# BoardB-USB.net
KiCad netlist of a schematic drawn in Altium Designer
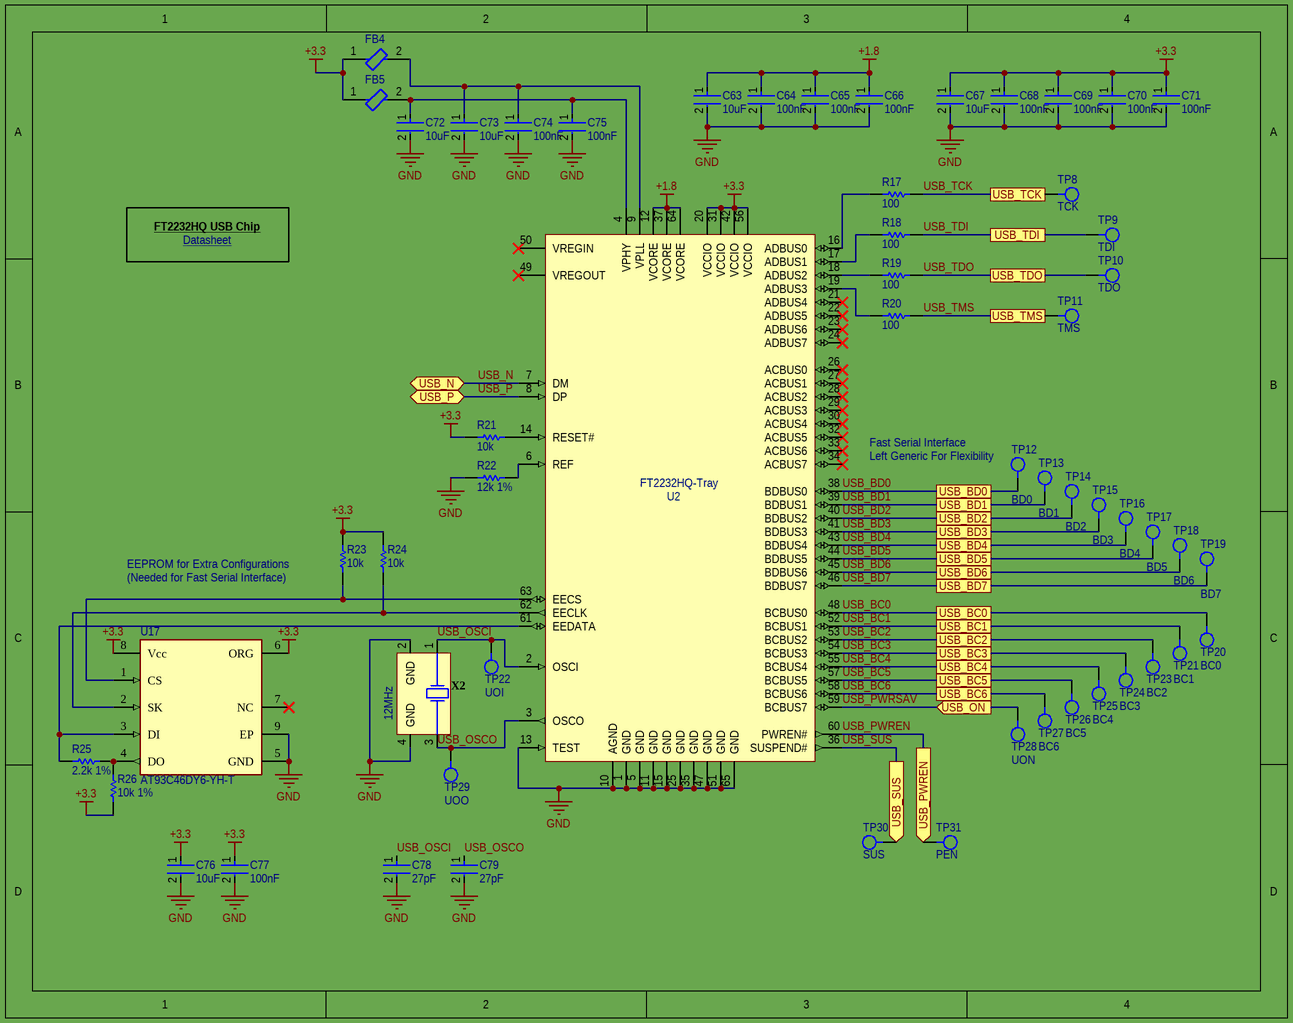
[diagram p0: BoardB-USB.SchDoc]

(export (version "E")
  (design (tool "Eeschema 10.0.6"))
  (components
    (comp (ref "C63")
      (value "10uF")
      (footprint "FP-GRM188-0_1-e0_2_0_55-IPC_A")
      (description "Chip Multilayer Ceramic Capacitors for General Purpose, 0603, 10uF, X5R, 15%, 20%, 6.3V")
      (fields (field (name "VOLTAGE") "6.3V") (field (name "TOLERANCE") "20%"))
      (libsource (lib "Altium Content Vault") (part "02cd4be3c70576c341d710602a673aa"))
    )
    (comp (ref "C64")
      (value "100nF")
      (footprint "FP-CGA3E-0_3-0_1-IPC_A")
      (description "Cap Ceramic 100nF 50V X7R 10% Pad SMD 0603 +125°C Automotive T/R")
      (fields (field (name "TOLERANCE") "10%") (field (name "VOLTAGE") "50V"))
      (libsource (lib "Altium Content Vault") (part "b4654b650e69147ec39a6b967a45e02"))
    )
    (comp (ref "C65")
      (value "100nF")
      (footprint "FP-CGA3E-0_3-0_1-IPC_A")
      (description "Cap Ceramic 100nF 50V X7R 10% Pad SMD 0603 +125°C Automotive T/R")
      (fields (field (name "TOLERANCE") "10%") (field (name "VOLTAGE") "50V"))
      (libsource (lib "Altium Content Vault") (part "b4654b650e69147ec39a6b967a45e02"))
    )
    (comp (ref "C66")
      (value "100nF")
      (footprint "FP-CGA3E-0_3-0_1-IPC_A")
      (description "Cap Ceramic 100nF 50V X7R 10% Pad SMD 0603 +125°C Automotive T/R")
      (fields (field (name "TOLERANCE") "10%") (field (name "VOLTAGE") "50V"))
      (libsource (lib "Altium Content Vault") (part "b4654b650e69147ec39a6b967a45e02"))
    )
    (comp (ref "C67")
      (value "10uF")
      (footprint "FP-GRM188-0_1-e0_2_0_55-IPC_A")
      (description "Chip Multilayer Ceramic Capacitors for General Purpose, 0603, 10uF, X5R, 15%, 20%, 6.3V")
      (fields (field (name "VOLTAGE") "6.3V") (field (name "TOLERANCE") "20%"))
      (libsource (lib "Altium Content Vault") (part "02cd4be3c70576c341d710602a673aa"))
    )
    (comp (ref "C68")
      (value "100nF")
      (footprint "FP-CGA3E-0_3-0_1-IPC_A")
      (description "Cap Ceramic 100nF 50V X7R 10% Pad SMD 0603 +125°C Automotive T/R")
      (fields (field (name "TOLERANCE") "10%") (field (name "VOLTAGE") "50V"))
      (libsource (lib "Altium Content Vault") (part "b4654b650e69147ec39a6b967a45e02"))
    )
    (comp (ref "C69")
      (value "100nF")
      (footprint "FP-CGA3E-0_3-0_1-IPC_A")
      (description "Cap Ceramic 100nF 50V X7R 10% Pad SMD 0603 +125°C Automotive T/R")
      (fields (field (name "TOLERANCE") "10%") (field (name "VOLTAGE") "50V"))
      (libsource (lib "Altium Content Vault") (part "b4654b650e69147ec39a6b967a45e02"))
    )
    (comp (ref "C70")
      (value "100nF")
      (footprint "FP-CGA3E-0_3-0_1-IPC_A")
      (description "Cap Ceramic 100nF 50V X7R 10% Pad SMD 0603 +125°C Automotive T/R")
      (fields (field (name "TOLERANCE") "10%") (field (name "VOLTAGE") "50V"))
      (libsource (lib "Altium Content Vault") (part "b4654b650e69147ec39a6b967a45e02"))
    )
    (comp (ref "C71")
      (value "100nF")
      (footprint "FP-CGA3E-0_3-0_1-IPC_A")
      (description "Cap Ceramic 100nF 50V X7R 10% Pad SMD 0603 +125°C Automotive T/R")
      (fields (field (name "TOLERANCE") "10%") (field (name "VOLTAGE") "50V"))
      (libsource (lib "Altium Content Vault") (part "b4654b650e69147ec39a6b967a45e02"))
    )
    (comp (ref "C72")
      (value "10uF")
      (footprint "FP-GRM188-0_1-e0_2_0_55-IPC_A")
      (description "Chip Multilayer Ceramic Capacitors for General Purpose, 0603, 10uF, X5R, 15%, 20%, 6.3V")
      (fields (field (name "VOLTAGE") "6.3V") (field (name "TOLERANCE") "20%"))
      (libsource (lib "Altium Content Vault") (part "02cd4be3c70576c341d710602a673aa"))
    )
    (comp (ref "C73")
      (value "10uF")
      (footprint "FP-GRM188-0_1-e0_2_0_55-IPC_A")
      (description "Chip Multilayer Ceramic Capacitors for General Purpose, 0603, 10uF, X5R, 15%, 20%, 6.3V")
      (fields (field (name "VOLTAGE") "6.3V") (field (name "TOLERANCE") "20%"))
      (libsource (lib "Altium Content Vault") (part "02cd4be3c70576c341d710602a673aa"))
    )
    (comp (ref "C74")
      (value "100nF")
      (footprint "FP-CGA3E-0_3-0_1-IPC_A")
      (description "Cap Ceramic 100nF 50V X7R 10% Pad SMD 0603 +125°C Automotive T/R")
      (fields (field (name "TOLERANCE") "10%") (field (name "VOLTAGE") "50V"))
      (libsource (lib "Altium Content Vault") (part "b4654b650e69147ec39a6b967a45e02"))
    )
    (comp (ref "C75")
      (value "100nF")
      (footprint "FP-CGA3E-0_3-0_1-IPC_A")
      (description "Cap Ceramic 100nF 50V X7R 10% Pad SMD 0603 +125°C Automotive T/R")
      (fields (field (name "TOLERANCE") "10%") (field (name "VOLTAGE") "50V"))
      (libsource (lib "Altium Content Vault") (part "b4654b650e69147ec39a6b967a45e02"))
    )
    (comp (ref "C76")
      (value "10uF")
      (footprint "FP-GRM188-0_1-e0_2_0_55-IPC_A")
      (description "Chip Multilayer Ceramic Capacitors for General Purpose, 0603, 10uF, X5R, 15%, 20%, 6.3V")
      (fields (field (name "VOLTAGE") "6.3V") (field (name "TOLERANCE") "20%"))
      (libsource (lib "Altium Content Vault") (part "02cd4be3c70576c341d710602a673aa"))
    )
    (comp (ref "C77")
      (value "100nF")
      (footprint "FP-CGA3E-0_3-0_1-IPC_A")
      (description "Cap Ceramic 100nF 50V X7R 10% Pad SMD 0603 +125°C Automotive T/R")
      (fields (field (name "TOLERANCE") "10%") (field (name "VOLTAGE") "50V"))
      (libsource (lib "Altium Content Vault") (part "b4654b650e69147ec39a6b967a45e02"))
    )
    (comp (ref "C78")
      (value "27pF")
      (footprint "FP-C0402-BB-MFG")
      (description "CAP CER 27PF 50V C0G/NP0 0402")
      (fields (field (name "MANUFACTURER") "Kemet") (field (name "TOLERANCE") "0.05"))
      (libsource (lib "Altium Content Vault") (part "b4654b650e69147ec39a6b967a45e02"))
    )
    (comp (ref "C79")
      (value "27pF")
      (footprint "FP-C0402-BB-MFG")
      (description "CAP CER 27PF 50V C0G/NP0 0402")
      (fields (field (name "MANUFACTURER") "Kemet") (field (name "TOLERANCE") "0.05"))
      (libsource (lib "Altium Content Vault") (part "b4654b650e69147ec39a6b967a45e02"))
    )
    (comp (ref "FB4")
      (value "BLM18AG601SN1D")
      (footprint "FP-BLM18-0_15-t0_8-MFG")
      (description "Chip Ferrite Bead, 0603, 600Ω @ 100MHz, 0.38Ω, 25%, 500mA")
      (fields (field (name "TOLERANCE") "25%"))
      (libsource (lib "Altium Content Vault") (part "5f30dd21d616792df468990f7003faa"))
    )
    (comp (ref "FB5")
      (value "BLM18AG601SN1D")
      (footprint "FP-BLM18-0_15-t0_8-MFG")
      (description "Chip Ferrite Bead, 0603, 600Ω @ 100MHz, 0.38Ω, 25%, 500mA")
      (fields (field (name "TOLERANCE") "25%"))
      (libsource (lib "Altium Content Vault") (part "5f30dd21d616792df468990f7003faa"))
    )
    (comp (ref "R17")
      (value "100")
      (footprint "RESC1005X40X25ML05T10")
      (fields (field (name "PART NUMBER") "RC0402FR-07100RL") (field (name "MANUFACTURER") "Yageo / Phycomp"))
      (libsource (lib "Altium Content Vault") (part "RES"))
    )
    (comp (ref "R18")
      (value "100")
      (footprint "RESC1005X40X25ML05T10")
      (fields (field (name "PART NUMBER") "RC0402FR-07100RL") (field (name "MANUFACTURER") "Yageo / Phycomp"))
      (libsource (lib "Altium Content Vault") (part "RES"))
    )
    (comp (ref "R19")
      (value "100")
      (footprint "RESC1005X40X25ML05T10")
      (fields (field (name "PART NUMBER") "RC0402FR-07100RL") (field (name "MANUFACTURER") "Yageo / Phycomp"))
      (libsource (lib "Altium Content Vault") (part "RES"))
    )
    (comp (ref "R20")
      (value "100")
      (footprint "RESC1005X40X25ML05T10")
      (fields (field (name "PART NUMBER") "RC0402FR-07100RL") (field (name "MANUFACTURER") "Yageo / Phycomp"))
      (libsource (lib "Altium Content Vault") (part "RES"))
    )
    (comp (ref "R21")
      (value "10k")
      (footprint "RESC1005X40X25LL05T05")
      (description "Chip Resistor, 10 KOhm, +/- 1%, 0.1 W, -55 to 155 degC, 0402 (1005 Metric), RoHS, Tape and Reel")
      (fields (field (name "TOLERANCE") "1%") (field (name "MANUFACTURER") "Panasonic"))
      (libsource (lib "Altium Content Vault") (part "RES-2"))
    )
    (comp (ref "R22")
      (value "12k 1%")
      (footprint "RESC1005X40X25ML05T05")
      (description "Chip Resistor, 12 KOhm, +/- 1%, 0.1 W, -55 to 155 degC, 0402 (1005 Metric), RoHS, Tape and Reel")
      (fields (field (name "TOLERANCE") "1%") (field (name "PARTNUMBER") "ERJ-2RKF1202X"))
      (libsource (lib "Altium Content Vault") (part "RES-2"))
    )
    (comp (ref "R23")
      (value "10k")
      (footprint "RESC1005X40X25LL05T05")
      (description "Chip Resistor, 10 KOhm, +/- 1%, 0.1 W, -55 to 155 degC, 0402 (1005 Metric), RoHS, Tape and Reel")
      (fields (field (name "TOLERANCE") "1%") (field (name "MANUFACTURER") "Panasonic"))
      (libsource (lib "Altium Content Vault") (part "RES-2"))
    )
    (comp (ref "R24")
      (value "10k")
      (footprint "RESC1005X40X25LL05T05")
      (description "Chip Resistor, 10 KOhm, +/- 1%, 0.1 W, -55 to 155 degC, 0402 (1005 Metric), RoHS, Tape and Reel")
      (fields (field (name "TOLERANCE") "1%") (field (name "MANUFACTURER") "Panasonic"))
      (libsource (lib "Altium Content Vault") (part "RES-2"))
    )
    (comp (ref "R25")
      (value "2.2k 1%")
      (footprint "RESC1005X40X25NL05T10")
      (fields (field (name "MANUFACTURER") "Yageo / Phycomp") (field (name "PART NUMBER") "RC0402FR-072K2L"))
      (libsource (lib "Altium Content Vault") (part "RES"))
    )
    (comp (ref "R26")
      (value "10k 1%")
      (footprint "RESC1005X40X25LL05T05")
      (description "Chip Resistor, 10 KOhm, +/- 1%, 0.1 W, -55 to 155 degC, 0402 (1005 Metric), RoHS, Tape and Reel")
      (fields (field (name "TOLERANCE") "1%") (field (name "MANUFACTURER") "Panasonic"))
      (libsource (lib "Altium Content Vault") (part "RES-2"))
    )
    (comp (ref "TP8")
      (value "TCK")
      (footprint "TestPoint1mm")
      (description "Test Point 1mm Diameter")
      (libsource (lib "Virtex") (part "TestPoint1mm"))
    )
    (comp (ref "TP9")
      (value "TDI")
      (footprint "TestPoint1mm")
      (description "Test Point 1mm Diameter")
      (libsource (lib "Virtex") (part "TestPoint1mm"))
    )
    (comp (ref "TP10")
      (value "TDO")
      (footprint "TestPoint1mm")
      (description "Test Point 1mm Diameter")
      (libsource (lib "Virtex") (part "TestPoint1mm"))
    )
    (comp (ref "TP11")
      (value "TMS")
      (footprint "TestPoint1mm")
      (description "Test Point 1mm Diameter")
      (libsource (lib "Virtex") (part "TestPoint1mm"))
    )
    (comp (ref "TP12")
      (value "BD0")
      (footprint "TestPoint1mm")
      (description "Test Point 1mm Diameter")
      (libsource (lib "Virtex") (part "TestPoint1mm"))
    )
    (comp (ref "TP13")
      (value "BD1")
      (footprint "TestPoint1mm")
      (description "Test Point 1mm Diameter")
      (libsource (lib "Virtex") (part "TestPoint1mm"))
    )
    (comp (ref "TP14")
      (value "BD2")
      (footprint "TestPoint1mm")
      (description "Test Point 1mm Diameter")
      (libsource (lib "Virtex") (part "TestPoint1mm"))
    )
    (comp (ref "TP15")
      (value "BD3")
      (footprint "TestPoint1mm")
      (description "Test Point 1mm Diameter")
      (libsource (lib "Virtex") (part "TestPoint1mm"))
    )
    (comp (ref "TP16")
      (value "BD4")
      (footprint "TestPoint1mm")
      (description "Test Point 1mm Diameter")
      (libsource (lib "Virtex") (part "TestPoint1mm"))
    )
    (comp (ref "TP17")
      (value "BD5")
      (footprint "TestPoint1mm")
      (description "Test Point 1mm Diameter")
      (libsource (lib "Virtex") (part "TestPoint1mm"))
    )
    (comp (ref "TP18")
      (value "BD6")
      (footprint "TestPoint1mm")
      (description "Test Point 1mm Diameter")
      (libsource (lib "Virtex") (part "TestPoint1mm"))
    )
    (comp (ref "TP19")
      (value "BD7")
      (footprint "TestPoint1mm")
      (description "Test Point 1mm Diameter")
      (libsource (lib "Virtex") (part "TestPoint1mm"))
    )
    (comp (ref "TP20")
      (value "BC0")
      (footprint "TestPoint1mm")
      (description "Test Point 1mm Diameter")
      (libsource (lib "Virtex") (part "TestPoint1mm"))
    )
    (comp (ref "TP21")
      (value "BC1")
      (footprint "TestPoint1mm")
      (description "Test Point 1mm Diameter")
      (libsource (lib "Virtex") (part "TestPoint1mm"))
    )
    (comp (ref "TP22")
      (value "UOI")
      (footprint "TestPoint1mm")
      (description "Test Point 1mm Diameter")
      (libsource (lib "Virtex") (part "TestPoint1mm"))
    )
    (comp (ref "TP23")
      (value "BC2")
      (footprint "TestPoint1mm")
      (description "Test Point 1mm Diameter")
      (libsource (lib "Virtex") (part "TestPoint1mm"))
    )
    (comp (ref "TP24")
      (value "BC3")
      (footprint "TestPoint1mm")
      (description "Test Point 1mm Diameter")
      (libsource (lib "Virtex") (part "TestPoint1mm"))
    )
    (comp (ref "TP25")
      (value "BC4")
      (footprint "TestPoint1mm")
      (description "Test Point 1mm Diameter")
      (libsource (lib "Virtex") (part "TestPoint1mm"))
    )
    (comp (ref "TP26")
      (value "BC5")
      (footprint "TestPoint1mm")
      (description "Test Point 1mm Diameter")
      (libsource (lib "Virtex") (part "TestPoint1mm"))
    )
    (comp (ref "TP27")
      (value "BC6")
      (footprint "TestPoint1mm")
      (description "Test Point 1mm Diameter")
      (libsource (lib "Virtex") (part "TestPoint1mm"))
    )
    (comp (ref "TP28")
      (value "UON")
      (footprint "TestPoint1mm")
      (description "Test Point 1mm Diameter")
      (libsource (lib "Virtex") (part "TestPoint1mm"))
    )
    (comp (ref "TP29")
      (value "UOO")
      (footprint "TestPoint1mm")
      (description "Test Point 1mm Diameter")
      (libsource (lib "Virtex") (part "TestPoint1mm"))
    )
    (comp (ref "TP30")
      (value "SUS")
      (footprint "TestPoint1mm")
      (description "Test Point 1mm Diameter")
      (libsource (lib "Virtex") (part "TestPoint1mm"))
    )
    (comp (ref "TP31")
      (value "PEN")
      (footprint "TestPoint1mm")
      (description "Test Point 1mm Diameter")
      (libsource (lib "Virtex") (part "TestPoint1mm"))
    )
    (comp (ref "U2")
      (value "FT2232HQ-Tray")
      (footprint "QFN64_2_N")
      (description "Dual High Speed USB To Multipurpose UART/FIFO IC, 64-pin QFN, Tray")
      (fields (field (name "MANUFACTURER") "FTDI"))
      (libsource (lib "Altium Content Vault") (part "COM-UART-FT2232H-QFN64"))
    )
    (comp (ref "U17")
      (value "AT93C46DY6-YH-T")
      (footprint "FP-C04-21355-Q4B-IPC_C")
      (description "IC EEPROM 1KBIT SPI 8MINI MAP")
      (libsource (lib "Altium Content Vault") (part "38d5b16ef365a7a64ac37fa7d10f17c"))
    )
    (comp (ref "X2")
      (value "ABM8G-12.000MHZ-4Y-T3")
      (footprint "ABM8G-12.000MHZ-4Y-T3")
      (description "ABRACON - ABM8G-12.000MHZ-4Y-T3 - CRYSTAL, 12MHZ, 10PF, 3.2 X 2.5MM")
      (fields (field (name "MANUFACTURER") "Abracon"))
      (libsource (lib "BoardA") (part "ABM8G-12.000MHZ-4Y-T3"))
    )
  )
  (nets
    (net (code "1") (name "+1.8") (class "Default")
      (node (ref "C63") (pin "1") (pinfunction "1_1") (pintype "passive"))
      (node (ref "C64") (pin "1") (pinfunction "1_1") (pintype "passive"))
      (node (ref "C65") (pin "1") (pinfunction "1_1") (pintype "passive"))
      (node (ref "C66") (pin "1") (pinfunction "1_1") (pintype "passive"))
      (node (ref "U2") (pin "12") (pinfunction "VCORE_12") (pintype "power_in"))
      (node (ref "U2") (pin "37") (pinfunction "VCORE_37") (pintype "power_in"))
      (node (ref "U2") (pin "64") (pinfunction "VCORE_64") (pintype "power_in"))
    )
    (net (code "2") (name "+3.3") (class "Default")
      (node (ref "C67") (pin "1") (pinfunction "1_1") (pintype "passive"))
      (node (ref "C68") (pin "1") (pinfunction "1_1") (pintype "passive"))
      (node (ref "C69") (pin "1") (pinfunction "1_1") (pintype "passive"))
      (node (ref "C70") (pin "1") (pinfunction "1_1") (pintype "passive"))
      (node (ref "C71") (pin "1") (pinfunction "1_1") (pintype "passive"))
      (node (ref "C76") (pin "1") (pinfunction "1_1") (pintype "passive"))
      (node (ref "C77") (pin "1") (pinfunction "1_1") (pintype "passive"))
      (node (ref "FB4") (pin "1") (pinfunction "1_1") (pintype "passive"))
      (node (ref "FB5") (pin "1") (pinfunction "1_1") (pintype "passive"))
      (node (ref "R21") (pin "2") (pinfunction "2_2") (pintype "passive"))
      (node (ref "R23") (pin "2") (pinfunction "2_2") (pintype "passive"))
      (node (ref "R24") (pin "2") (pinfunction "2_2") (pintype "passive"))
      (node (ref "R26") (pin "1") (pinfunction "1_1") (pintype "passive"))
      (node (ref "U17") (pin "6") (pinfunction "ORG_6") (pintype "passive"))
      (node (ref "U17") (pin "8") (pinfunction "Vcc_8") (pintype "power_in"))
      (node (ref "U2") (pin "20") (pinfunction "VCCIO_20") (pintype "power_in"))
      (node (ref "U2") (pin "31") (pinfunction "VCCIO_31") (pintype "power_in"))
      (node (ref "U2") (pin "42") (pinfunction "VCCIO_42") (pintype "power_in"))
      (node (ref "U2") (pin "56") (pinfunction "VCCIO_56") (pintype "power_in"))
    )
    (net (code "3") (name "/USB_BC0") (class "Default")
      (node (ref "TP20") (pin "1") (pintype "passive"))
      (node (ref "U2") (pin "48") (pinfunction "BCBUS0_48") (pintype "bidirectional"))
    )
    (net (code "4") (name "/USB_BC1") (class "Default")
      (node (ref "TP21") (pin "1") (pintype "passive"))
      (node (ref "U2") (pin "52") (pinfunction "BCBUS1_52") (pintype "bidirectional"))
    )
    (net (code "5") (name "/USB_BC2") (class "Default")
      (node (ref "TP23") (pin "1") (pintype "passive"))
      (node (ref "U2") (pin "53") (pinfunction "BCBUS2_53") (pintype "bidirectional"))
    )
    (net (code "6") (name "/USB_BC3") (class "Default")
      (node (ref "TP24") (pin "1") (pintype "passive"))
      (node (ref "U2") (pin "54") (pinfunction "BCBUS3_54") (pintype "bidirectional"))
    )
    (net (code "7") (name "/USB_BC4") (class "Default")
      (node (ref "TP25") (pin "1") (pintype "passive"))
      (node (ref "U2") (pin "55") (pinfunction "BCBUS4_55") (pintype "bidirectional"))
    )
    (net (code "8") (name "/USB_BC5") (class "Default")
      (node (ref "TP26") (pin "1") (pintype "passive"))
      (node (ref "U2") (pin "57") (pinfunction "BCBUS5_57") (pintype "bidirectional"))
    )
    (net (code "9") (name "/USB_BC6") (class "Default")
      (node (ref "TP27") (pin "1") (pintype "passive"))
      (node (ref "U2") (pin "58") (pinfunction "BCBUS6_58") (pintype "bidirectional"))
    )
    (net (code "10") (name "/USB_BD0") (class "Default")
      (node (ref "TP12") (pin "1") (pintype "passive"))
      (node (ref "U2") (pin "38") (pinfunction "BDBUS0_38") (pintype "bidirectional"))
    )
    (net (code "11") (name "/USB_BD1") (class "Default")
      (node (ref "TP13") (pin "1") (pintype "passive"))
      (node (ref "U2") (pin "39") (pinfunction "BDBUS1_39") (pintype "bidirectional"))
    )
    (net (code "12") (name "/USB_BD2") (class "Default")
      (node (ref "TP14") (pin "1") (pintype "passive"))
      (node (ref "U2") (pin "40") (pinfunction "BDBUS2_40") (pintype "bidirectional"))
    )
    (net (code "13") (name "/USB_BD3") (class "Default")
      (node (ref "TP15") (pin "1") (pintype "passive"))
      (node (ref "U2") (pin "41") (pinfunction "BDBUS3_41") (pintype "bidirectional"))
    )
    (net (code "14") (name "/USB_BD4") (class "Default")
      (node (ref "TP16") (pin "1") (pintype "passive"))
      (node (ref "U2") (pin "43") (pinfunction "BDBUS4_43") (pintype "bidirectional"))
    )
    (net (code "15") (name "/USB_BD5") (class "Default")
      (node (ref "TP17") (pin "1") (pintype "passive"))
      (node (ref "U2") (pin "44") (pinfunction "BDBUS5_44") (pintype "bidirectional"))
    )
    (net (code "16") (name "/USB_BD6") (class "Default")
      (node (ref "TP18") (pin "1") (pintype "passive"))
      (node (ref "U2") (pin "45") (pinfunction "BDBUS6_45") (pintype "bidirectional"))
    )
    (net (code "17") (name "/USB_BD7") (class "Default")
      (node (ref "TP19") (pin "1") (pintype "passive"))
      (node (ref "U2") (pin "46") (pinfunction "BDBUS7_46") (pintype "bidirectional"))
    )
    (net (code "18") (name "/USB_N") (class "Default")
      (node (ref "U2") (pin "7") (pinfunction "DM_7") (pintype "input"))
    )
    (net (code "19") (name "/USB_OSCI") (class "Default")
      (node (ref "C78") (pin "1") (pinfunction "1_1") (pintype "passive"))
      (node (ref "TP22") (pin "1") (pintype "passive"))
      (node (ref "U2") (pin "2") (pinfunction "OSCI_2") (pintype "input"))
      (node (ref "X2") (pin "1") (pintype "passive"))
    )
    (net (code "20") (name "/USB_OSCO") (class "Default")
      (node (ref "C79") (pin "1") (pinfunction "1_1") (pintype "passive"))
      (node (ref "TP29") (pin "1") (pintype "passive"))
      (node (ref "U2") (pin "3") (pinfunction "OSCO_3") (pintype "output"))
      (node (ref "X2") (pin "3") (pintype "passive"))
    )
    (net (code "21") (name "/USB_P") (class "Default")
      (node (ref "U2") (pin "8") (pinfunction "DP_8") (pintype "input"))
    )
    (net (code "22") (name "/USB_PWREN") (class "Default")
      (node (ref "TP31") (pin "1") (pintype "passive"))
      (node (ref "U2") (pin "60") (pinfunction "PWREN#_60") (pintype "output"))
    )
    (net (code "23") (name "/USB_PWRSAV") (class "Default")
      (node (ref "TP28") (pin "1") (pintype "passive"))
      (node (ref "U2") (pin "59") (pinfunction "BCBUS7_59") (pintype "bidirectional"))
    )
    (net (code "24") (name "/USB_SUS") (class "Default")
      (node (ref "TP30") (pin "1") (pintype "passive"))
      (node (ref "U2") (pin "36") (pinfunction "SUSPEND#_36") (pintype "output"))
    )
    (net (code "25") (name "/USB_TCK") (class "Default")
      (node (ref "R17") (pin "2") (pinfunction "2_2") (pintype "passive"))
      (node (ref "TP8") (pin "1") (pintype "passive"))
    )
    (net (code "26") (name "/USB_TDI") (class "Default")
      (node (ref "R18") (pin "2") (pinfunction "2_2") (pintype "passive"))
      (node (ref "TP9") (pin "1") (pintype "passive"))
    )
    (net (code "27") (name "/USB_TDO") (class "Default")
      (node (ref "R19") (pin "2") (pinfunction "2_2") (pintype "passive"))
      (node (ref "TP10") (pin "1") (pintype "passive"))
    )
    (net (code "28") (name "/USB_TMS") (class "Default")
      (node (ref "R20") (pin "2") (pinfunction "2_2") (pintype "passive"))
      (node (ref "TP11") (pin "1") (pintype "passive"))
    )
    (net (code "29") (name "GND") (class "Default")
      (node (ref "C63") (pin "2") (pinfunction "2_2") (pintype "passive"))
      (node (ref "C64") (pin "2") (pinfunction "2_2") (pintype "passive"))
      (node (ref "C65") (pin "2") (pinfunction "2_2") (pintype "passive"))
      (node (ref "C66") (pin "2") (pinfunction "2_2") (pintype "passive"))
      (node (ref "C67") (pin "2") (pinfunction "2_2") (pintype "passive"))
      (node (ref "C68") (pin "2") (pinfunction "2_2") (pintype "passive"))
      (node (ref "C69") (pin "2") (pinfunction "2_2") (pintype "passive"))
      (node (ref "C70") (pin "2") (pinfunction "2_2") (pintype "passive"))
      (node (ref "C71") (pin "2") (pinfunction "2_2") (pintype "passive"))
      (node (ref "C72") (pin "2") (pinfunction "2_2") (pintype "passive"))
      (node (ref "C73") (pin "2") (pinfunction "2_2") (pintype "passive"))
      (node (ref "C74") (pin "2") (pinfunction "2_2") (pintype "passive"))
      (node (ref "C75") (pin "2") (pinfunction "2_2") (pintype "passive"))
      (node (ref "C76") (pin "2") (pinfunction "2_2") (pintype "passive"))
      (node (ref "C77") (pin "2") (pinfunction "2_2") (pintype "passive"))
      (node (ref "C78") (pin "2") (pinfunction "2_2") (pintype "passive"))
      (node (ref "C79") (pin "2") (pinfunction "2_2") (pintype "passive"))
      (node (ref "R22") (pin "1") (pinfunction "1_1") (pintype "passive"))
      (node (ref "U17") (pin "5") (pinfunction "GND_5") (pintype "power_in"))
      (node (ref "U17") (pin "9") (pinfunction "EP_9") (pintype "passive"))
      (node (ref "U2") (pin "1") (pinfunction "GND_1") (pintype "power_in"))
      (node (ref "U2") (pin "10") (pinfunction "AGND_10") (pintype "power_in"))
      (node (ref "U2") (pin "11") (pinfunction "GND_11") (pintype "power_in"))
      (node (ref "U2") (pin "13") (pinfunction "TEST_13") (pintype "input"))
      (node (ref "U2") (pin "15") (pinfunction "GND_15") (pintype "power_in"))
      (node (ref "U2") (pin "25") (pinfunction "GND_25") (pintype "power_in"))
      (node (ref "U2") (pin "35") (pinfunction "GND_35") (pintype "power_in"))
      (node (ref "U2") (pin "47") (pinfunction "GND_47") (pintype "power_in"))
      (node (ref "U2") (pin "5") (pinfunction "GND_5") (pintype "power_in"))
      (node (ref "U2") (pin "51") (pinfunction "GND_51") (pintype "power_in"))
      (node (ref "U2") (pin "65") (pinfunction "GND_65") (pintype "power_in"))
      (node (ref "X2") (pin "2") (pinfunction "GND_2") (pintype "power_in"))
      (node (ref "X2") (pin "4") (pinfunction "GND_4") (pintype "power_in"))
    )
    (net (code "30") (name "Net-(U2-ADBUS0)") (class "Default")
      (node (ref "R17") (pin "1") (pinfunction "1_1") (pintype "passive"))
      (node (ref "U2") (pin "16") (pinfunction "ADBUS0_16") (pintype "bidirectional"))
    )
    (net (code "31") (name "Net-(U2-ADBUS1)") (class "Default")
      (node (ref "R18") (pin "1") (pinfunction "1_1") (pintype "passive"))
      (node (ref "U2") (pin "17") (pinfunction "ADBUS1_17") (pintype "bidirectional"))
    )
    (net (code "32") (name "Net-(U2-ADBUS2)") (class "Default")
      (node (ref "R19") (pin "1") (pinfunction "1_1") (pintype "passive"))
      (node (ref "U2") (pin "18") (pinfunction "ADBUS2_18") (pintype "bidirectional"))
    )
    (net (code "33") (name "Net-(U2-ADBUS3)") (class "Default")
      (node (ref "R20") (pin "1") (pinfunction "1_1") (pintype "passive"))
      (node (ref "U2") (pin "19") (pinfunction "ADBUS3_19") (pintype "bidirectional"))
    )
    (net (code "34") (name "Net-(U2-REF)") (class "Default")
      (node (ref "R22") (pin "2") (pinfunction "2_2") (pintype "passive"))
      (node (ref "U2") (pin "6") (pinfunction "REF_6") (pintype "input"))
    )
    (net (code "35") (name "Net-(U2-RESET#)") (class "Default")
      (node (ref "R21") (pin "1") (pinfunction "1_1") (pintype "passive"))
      (node (ref "U2") (pin "14") (pinfunction "RESET#_14") (pintype "input"))
    )
    (net (code "36") (name "Net-(U2-VPHY)") (class "Default")
      (node (ref "C72") (pin "1") (pinfunction "1_1") (pintype "passive"))
      (node (ref "C75") (pin "1") (pinfunction "1_1") (pintype "passive"))
      (node (ref "FB5") (pin "2") (pinfunction "2_2") (pintype "passive"))
      (node (ref "U2") (pin "4") (pinfunction "VPHY_4") (pintype "power_in"))
    )
    (net (code "37") (name "Net-(U2-VPLL)") (class "Default")
      (node (ref "C73") (pin "1") (pinfunction "1_1") (pintype "passive"))
      (node (ref "C74") (pin "1") (pinfunction "1_1") (pintype "passive"))
      (node (ref "FB4") (pin "2") (pinfunction "2_2") (pintype "passive"))
      (node (ref "U2") (pin "9") (pinfunction "VPLL_9") (pintype "power_in"))
    )
    (net (code "38") (name "Net-(U17-CS)") (class "Default")
      (node (ref "R23") (pin "1") (pinfunction "1_1") (pintype "passive"))
      (node (ref "U17") (pin "1") (pinfunction "CS_1") (pintype "input"))
      (node (ref "U2") (pin "63") (pinfunction "EECS_63") (pintype "bidirectional"))
    )
    (net (code "39") (name "Net-(U17-DI)") (class "Default")
      (node (ref "R25") (pin "1") (pinfunction "1_1") (pintype "passive"))
      (node (ref "U17") (pin "3") (pinfunction "DI_3") (pintype "input"))
      (node (ref "U2") (pin "61") (pinfunction "EEDATA_61") (pintype "bidirectional"))
    )
    (net (code "40") (name "Net-(U17-DO)") (class "Default")
      (node (ref "R25") (pin "2") (pinfunction "2_2") (pintype "passive"))
      (node (ref "R26") (pin "2") (pinfunction "2_2") (pintype "passive"))
      (node (ref "U17") (pin "4") (pinfunction "DO_4") (pintype "output"))
    )
    (net (code "41") (name "Net-(U17-SK)") (class "Default")
      (node (ref "R24") (pin "1") (pinfunction "1_1") (pintype "passive"))
      (node (ref "U17") (pin "2") (pinfunction "SK_2") (pintype "input"))
      (node (ref "U2") (pin "62") (pinfunction "EECLK_62") (pintype "output"))
    )
    (net (code "42") (name "unconnected-(U2-ACBUS0-Pad26)") (class "Default")
      (node (ref "U2") (pin "26") (pinfunction "ACBUS0_26") (pintype "bidirectional+no_connect"))
    )
    (net (code "43") (name "unconnected-(U2-ACBUS1-Pad27)") (class "Default")
      (node (ref "U2") (pin "27") (pinfunction "ACBUS1_27") (pintype "bidirectional+no_connect"))
    )
    (net (code "44") (name "unconnected-(U2-ACBUS2-Pad28)") (class "Default")
      (node (ref "U2") (pin "28") (pinfunction "ACBUS2_28") (pintype "bidirectional+no_connect"))
    )
    (net (code "45") (name "unconnected-(U2-ACBUS3-Pad29)") (class "Default")
      (node (ref "U2") (pin "29") (pinfunction "ACBUS3_29") (pintype "bidirectional+no_connect"))
    )
    (net (code "46") (name "unconnected-(U2-ACBUS4-Pad30)") (class "Default")
      (node (ref "U2") (pin "30") (pinfunction "ACBUS4_30") (pintype "bidirectional+no_connect"))
    )
    (net (code "47") (name "unconnected-(U2-ACBUS5-Pad32)") (class "Default")
      (node (ref "U2") (pin "32") (pinfunction "ACBUS5_32") (pintype "bidirectional+no_connect"))
    )
    (net (code "48") (name "unconnected-(U2-ACBUS6-Pad33)") (class "Default")
      (node (ref "U2") (pin "33") (pinfunction "ACBUS6_33") (pintype "bidirectional+no_connect"))
    )
    (net (code "49") (name "unconnected-(U2-ACBUS7-Pad34)") (class "Default")
      (node (ref "U2") (pin "34") (pinfunction "ACBUS7_34") (pintype "bidirectional+no_connect"))
    )
    (net (code "50") (name "unconnected-(U2-ADBUS4-Pad21)") (class "Default")
      (node (ref "U2") (pin "21") (pinfunction "ADBUS4_21") (pintype "bidirectional+no_connect"))
    )
    (net (code "51") (name "unconnected-(U2-ADBUS5-Pad22)") (class "Default")
      (node (ref "U2") (pin "22") (pinfunction "ADBUS5_22") (pintype "bidirectional+no_connect"))
    )
    (net (code "52") (name "unconnected-(U2-ADBUS6-Pad23)") (class "Default")
      (node (ref "U2") (pin "23") (pinfunction "ADBUS6_23") (pintype "bidirectional+no_connect"))
    )
    (net (code "53") (name "unconnected-(U2-ADBUS7-Pad24)") (class "Default")
      (node (ref "U2") (pin "24") (pinfunction "ADBUS7_24") (pintype "bidirectional+no_connect"))
    )
    (net (code "54") (name "unconnected-(U2-VREGIN-Pad50)") (class "Default")
      (node (ref "U2") (pin "50") (pinfunction "VREGIN_50") (pintype "power_in+no_connect"))
    )
    (net (code "55") (name "unconnected-(U2-VREGOUT-Pad49)") (class "Default")
      (node (ref "U2") (pin "49") (pinfunction "VREGOUT_49") (pintype "power_in+no_connect"))
    )
    (net (code "56") (name "unconnected-(U17-NC-Pad7)") (class "Default")
      (node (ref "U17") (pin "7") (pinfunction "NC_7") (pintype "passive+no_connect"))
    )
  )
)
